# WavePainter_1_1.net
KiCad netlist of a schematic drawn in EAGLE
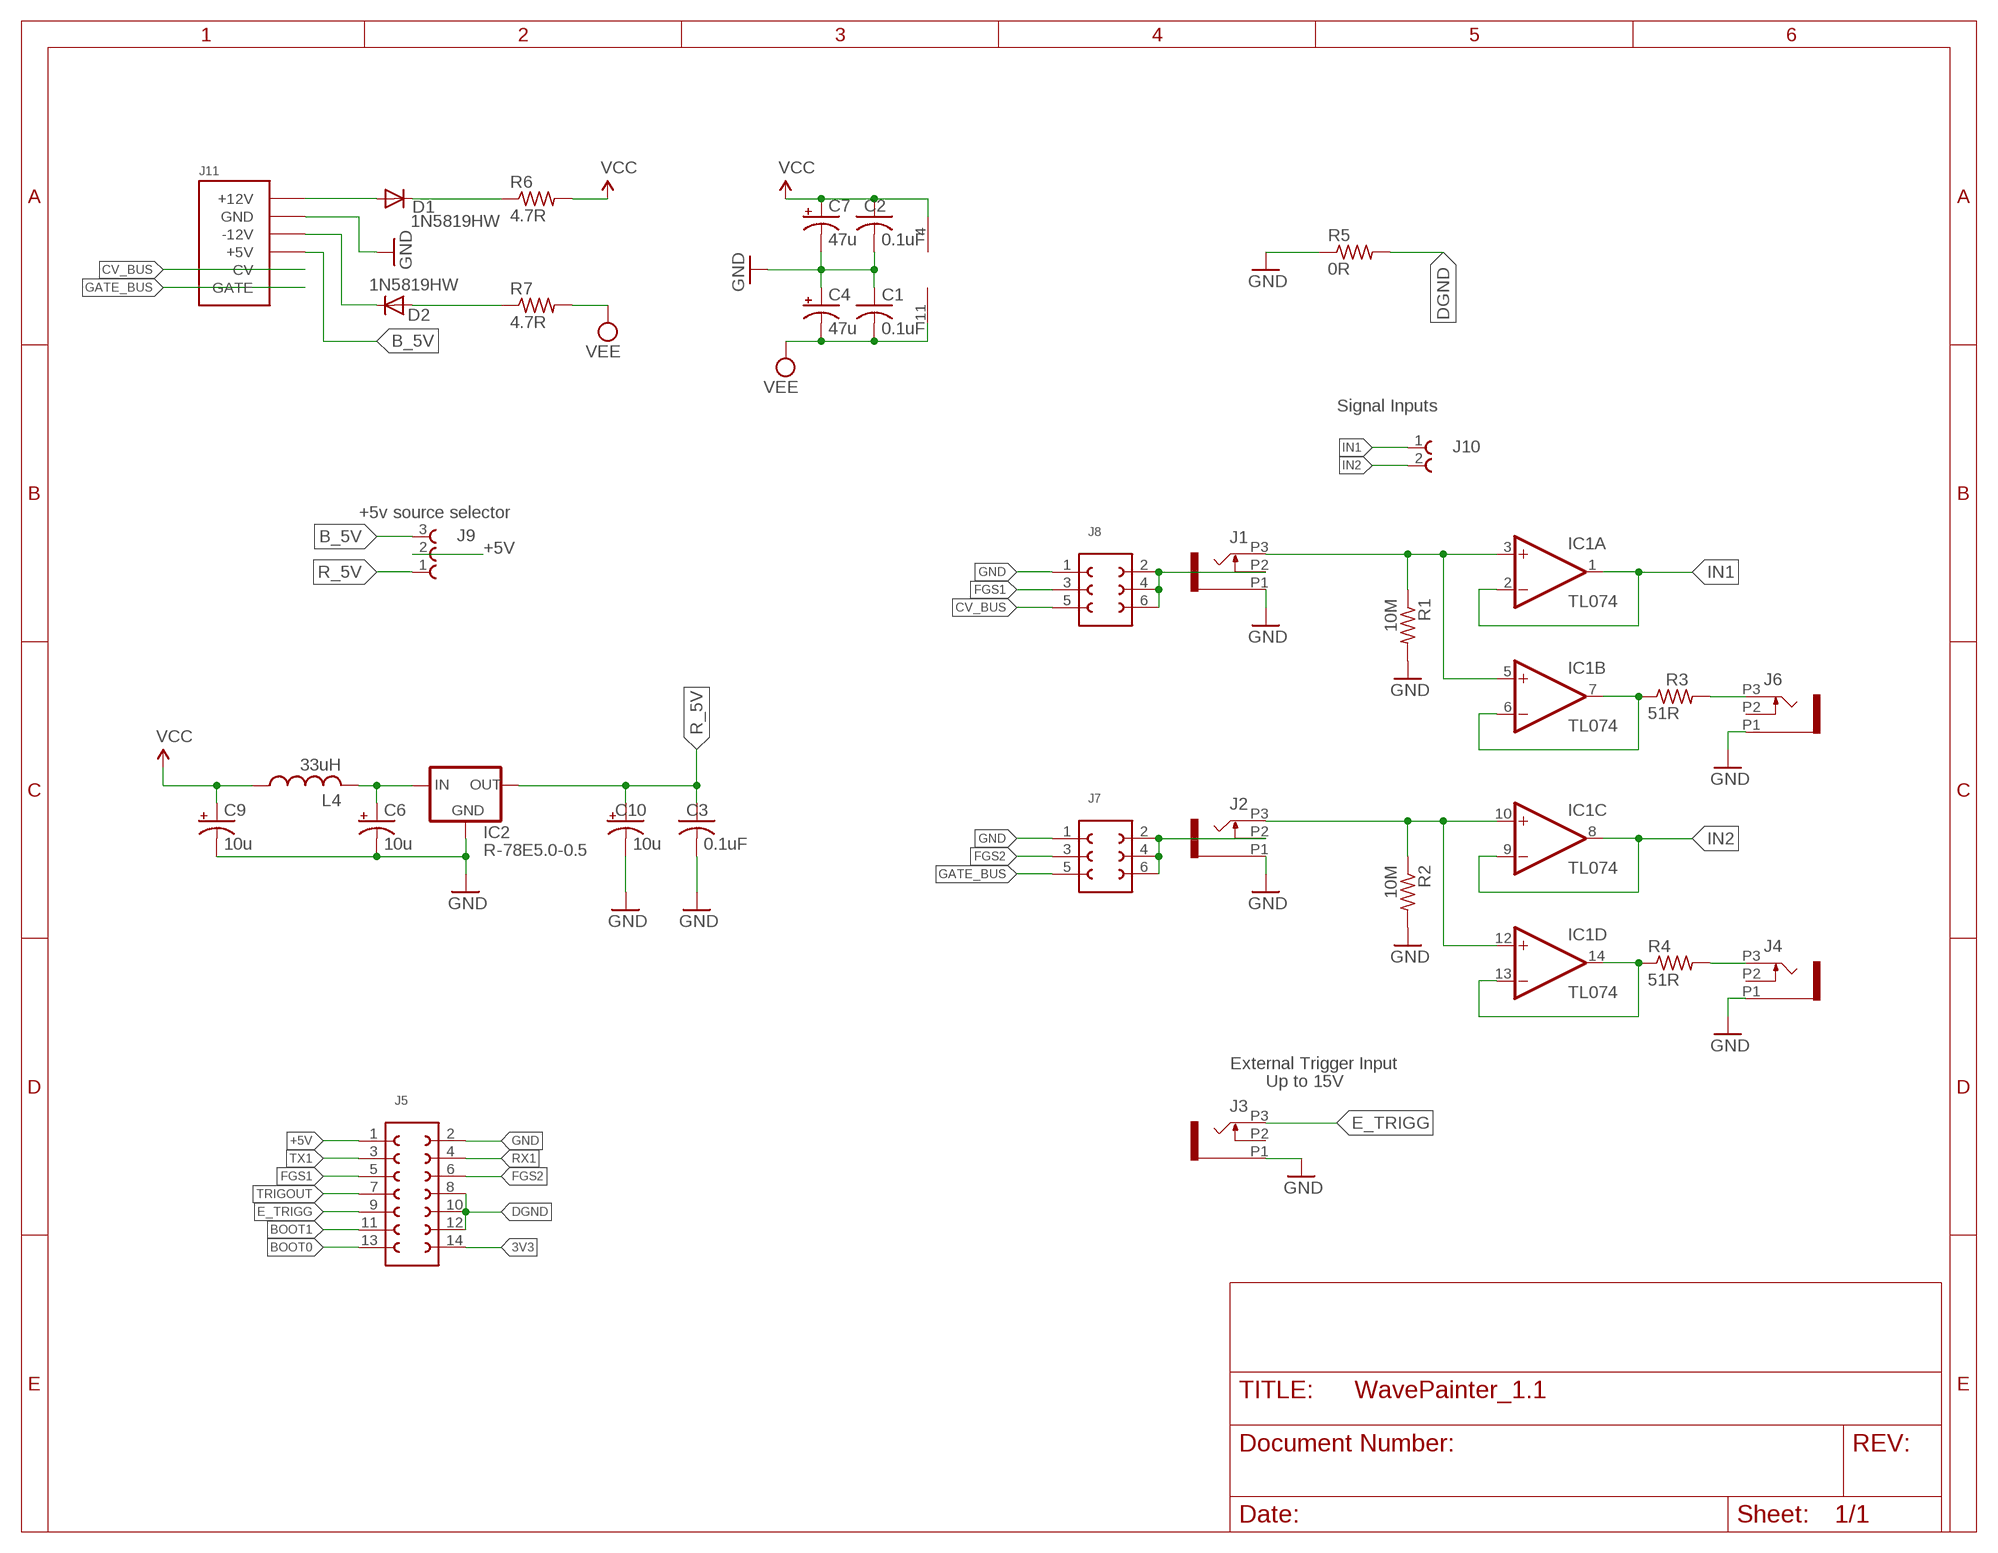
[diagram p0: schematic, sheet 1]

(export (version "E")
  (design (tool "Eeschema 10.0.6"))
  (components
    (comp (ref "C1")
      (value "0.1uF")
      (footprint "eagle-import:C0805")
      (libsource (lib "eagle-import") (part "C-USC0805"))
    )
    (comp (ref "C2")
      (value "0.1uF")
      (footprint "eagle-import:C0805")
      (libsource (lib "eagle-import") (part "C-USC0805"))
    )
    (comp (ref "C3")
      (value "0.1uF")
      (footprint "eagle-import:C0805")
      (libsource (lib "eagle-import") (part "C-USC0805"))
    )
    (comp (ref "C4")
      (value "47u")
      (footprint "eagle-import:PANASONIC_D")
      (libsource (lib "eagle-import") (part "CPOL-USD"))
    )
    (comp (ref "C6")
      (value "10u")
      (footprint "eagle-import:PANASONIC_B")
      (libsource (lib "eagle-import") (part "rcl_334_CPOL-USB"))
    )
    (comp (ref "C7")
      (value "47u")
      (footprint "eagle-import:PANASONIC_D")
      (libsource (lib "eagle-import") (part "CPOL-USD"))
    )
    (comp (ref "C9")
      (value "10u")
      (footprint "eagle-import:PANASONIC_B")
      (libsource (lib "eagle-import") (part "rcl_334_CPOL-USB"))
    )
    (comp (ref "C10")
      (value "10u")
      (footprint "eagle-import:PANASONIC_B")
      (libsource (lib "eagle-import") (part "rcl_334_CPOL-USB"))
    )
    (comp (ref "D1")
      (value "1N5819HW")
      (footprint "eagle-import:DIODE_SOD123")
      (libsource (lib "eagle-import") (part "DIODE_DIODE-SOD123"))
    )
    (comp (ref "D2")
      (value "1N5819HW")
      (footprint "eagle-import:DIODE_SOD123")
      (libsource (lib "eagle-import") (part "DIODE_DIODE-SOD123"))
    )
    (comp (ref "IC1")
      (value "TL074")
      (footprint "eagle-import:SO14")
      (libsource (lib "eagle-import") (part "TL074D"))
    )
    (comp (ref "IC2")
      (value "R-78E5.0-0.5")
      (footprint "eagle-import:SIP3")
      (fields (field (name "MF") "Recom") (field (name "MPN") "R-785.0-0.5"))
      (libsource (lib "eagle-import") (part "R-78E-0.55.0"))
    )
    (comp (ref "J1")
      (value "OG-PJ301_PJ301_THONKICONN7")
      (footprint "eagle-import:OG-PJ301_WQP_PJ_301M7")
      (libsource (lib "eagle-import") (part "OG-PJ301_PJ301_THONKICONN7"))
    )
    (comp (ref "J2")
      (value "OG-PJ301_PJ301_THONKICONN7")
      (footprint "eagle-import:OG-PJ301_WQP_PJ_301M7")
      (libsource (lib "eagle-import") (part "OG-PJ301_PJ301_THONKICONN7"))
    )
    (comp (ref "J3")
      (value "OG-PJ301_PJ301_THONKICONN7")
      (footprint "eagle-import:OG-PJ301_WQP_PJ_301M7")
      (libsource (lib "eagle-import") (part "OG-PJ301_PJ301_THONKICONN7"))
    )
    (comp (ref "J4")
      (value "OG-PJ301_PJ301_THONKICONN7")
      (footprint "eagle-import:OG-PJ301_WQP_PJ_301M7")
      (libsource (lib "eagle-import") (part "OG-PJ301_PJ301_THONKICONN7"))
    )
    (comp (ref "J5")
      (value "62001421821")
      (footprint "eagle-import:62001421821")
      (libsource (lib "eagle-import") (part "62001421821"))
    )
    (comp (ref "J6")
      (value "OG-PJ301_PJ301_THONKICONN7")
      (footprint "eagle-import:OG-PJ301_WQP_PJ_301M7")
      (libsource (lib "eagle-import") (part "OG-PJ301_PJ301_THONKICONN7"))
    )
    (comp (ref "J7")
      (value "61300621121")
      (footprint "eagle-import:61300621121")
      (libsource (lib "eagle-import") (part "61300621121"))
    )
    (comp (ref "J8")
      (value "61300621121")
      (footprint "eagle-import:61300621121")
      (libsource (lib "eagle-import") (part "61300621121"))
    )
    (comp (ref "J9")
      (value "61300311121")
      (footprint "eagle-import:61300311121")
      (libsource (lib "eagle-import") (part "61300311121"))
    )
    (comp (ref "J10")
      (value "61300211821")
      (footprint "eagle-import:61300211821")
      (libsource (lib "eagle-import") (part "61300211821"))
    )
    (comp (ref "J11")
      (value "POWER_SHROUDED_NOTEXT")
      (footprint "eagle-import:POWER_16_SHROUDED_NOTEXT")
      (libsource (lib "eagle-import") (part "POWER_SHROUDED_NOTEXT"))
    )
    (comp (ref "L4")
      (value "33uH")
      (footprint "eagle-import:L3225P")
      (libsource (lib "eagle-import") (part "L-USL3225P"))
    )
    (comp (ref "R1")
      (value "10M")
      (footprint "eagle-import:R0805")
      (libsource (lib "eagle-import") (part "R-US_R0805"))
    )
    (comp (ref "R2")
      (value "10M")
      (footprint "eagle-import:R0805")
      (libsource (lib "eagle-import") (part "R-US_R0805"))
    )
    (comp (ref "R3")
      (value "51R")
      (footprint "eagle-import:R0805")
      (libsource (lib "eagle-import") (part "R-US_R0805"))
    )
    (comp (ref "R4")
      (value "51R")
      (footprint "eagle-import:R0805")
      (libsource (lib "eagle-import") (part "R-US_R0805"))
    )
    (comp (ref "R5")
      (value "0R")
      (footprint "eagle-import:R0805")
      (libsource (lib "eagle-import") (part "R-US_R0805"))
    )
    (comp (ref "R6")
      (value "4.7R")
      (footprint "eagle-import:R1206")
      (libsource (lib "eagle-import") (part "R-US_R1206"))
    )
    (comp (ref "R7")
      (value "4.7R")
      (footprint "eagle-import:R1206")
      (libsource (lib "eagle-import") (part "R-US_R1206"))
    )
  )
  (nets
    (net (code "1") (name "+5V") (class "Default")
      (node (ref "J5") (pin "1") (pinfunction "1_1") (pintype "passive"))
      (node (ref "J9") (pin "2") (pinfunction "2_2") (pintype "passive"))
    )
    (net (code "2") (name "3V3") (class "Default")
      (node (ref "J5") (pin "14") (pinfunction "8_14") (pintype "passive"))
    )
    (net (code "3") (name "BOOT0") (class "Default")
      (node (ref "J5") (pin "13") (pinfunction "7_13") (pintype "passive"))
    )
    (net (code "4") (name "BOOT1") (class "Default")
      (node (ref "J5") (pin "11") (pinfunction "6_11") (pintype "passive"))
    )
    (net (code "5") (name "B_5V") (class "Default")
      (node (ref "J11") (pin "11") (pinfunction "+5V_11") (pintype "bidirectional"))
      (node (ref "J11") (pin "12") (pinfunction "+5V_12") (pintype "bidirectional"))
      (node (ref "J9") (pin "3") (pinfunction "1_3") (pintype "passive"))
    )
    (net (code "6") (name "CV_BUS") (class "Default")
      (node (ref "J11") (pin "13") (pinfunction "CV_13") (pintype "bidirectional"))
      (node (ref "J11") (pin "14") (pinfunction "CV_14") (pintype "bidirectional"))
      (node (ref "J8") (pin "5") (pinfunction "3_5") (pintype "passive"))
    )
    (net (code "7") (name "DGND") (class "Default")
      (node (ref "J5") (pin "10") (pinfunction "10_10") (pintype "passive"))
      (node (ref "J5") (pin "12") (pinfunction "9_12") (pintype "passive"))
      (node (ref "J5") (pin "8") (pinfunction "11_8") (pintype "passive"))
      (node (ref "R5") (pin "2") (pinfunction "2_2") (pintype "passive"))
    )
    (net (code "8") (name "E_TRIGG") (class "Default")
      (node (ref "J3") (pin "P3") (pinfunction "3_P3") (pintype "passive"))
      (node (ref "J5") (pin "9") (pinfunction "5_9") (pintype "passive"))
    )
    (net (code "9") (name "FGS1") (class "Default")
      (node (ref "J5") (pin "5") (pinfunction "3_5") (pintype "passive"))
      (node (ref "J8") (pin "3") (pinfunction "2_3") (pintype "passive"))
    )
    (net (code "10") (name "FGS2") (class "Default")
      (node (ref "J5") (pin "6") (pinfunction "12_6") (pintype "passive"))
      (node (ref "J7") (pin "3") (pinfunction "2_3") (pintype "passive"))
    )
    (net (code "11") (name "GATE_BUS") (class "Default")
      (node (ref "J11") (pin "15") (pinfunction "GATE_15") (pintype "bidirectional"))
      (node (ref "J11") (pin "16") (pinfunction "GATE_16") (pintype "bidirectional"))
      (node (ref "J7") (pin "5") (pinfunction "3_5") (pintype "passive"))
    )
    (net (code "12") (name "GND") (class "Default")
      (node (ref "C1") (pin "1") (pinfunction "1_1") (pintype "passive"))
      (node (ref "C10") (pin "-") (pinfunction "-_-") (pintype "passive"))
      (node (ref "C2") (pin "2") (pinfunction "2_2") (pintype "passive"))
      (node (ref "C3") (pin "2") (pinfunction "2_2") (pintype "passive"))
      (node (ref "C4") (pin "+") (pinfunction "+_+") (pintype "passive"))
      (node (ref "C6") (pin "-") (pinfunction "-_-") (pintype "passive"))
      (node (ref "C7") (pin "-") (pinfunction "-_-") (pintype "passive"))
      (node (ref "C9") (pin "-") (pinfunction "-_-") (pintype "passive"))
      (node (ref "IC2") (pin "2") (pinfunction "GND_2") (pintype "input"))
      (node (ref "J1") (pin "P1") (pinfunction "1_P1") (pintype "passive"))
      (node (ref "J11") (pin "3") (pinfunction "GND_3") (pintype "bidirectional"))
      (node (ref "J11") (pin "4") (pinfunction "GND_4") (pintype "bidirectional"))
      (node (ref "J11") (pin "5") (pinfunction "GND_5") (pintype "bidirectional"))
      (node (ref "J11") (pin "6") (pinfunction "GND_6") (pintype "bidirectional"))
      (node (ref "J11") (pin "7") (pinfunction "GND_7") (pintype "bidirectional"))
      (node (ref "J11") (pin "8") (pinfunction "GND_8") (pintype "bidirectional"))
      (node (ref "J2") (pin "P1") (pinfunction "1_P1") (pintype "passive"))
      (node (ref "J3") (pin "P1") (pinfunction "1_P1") (pintype "passive"))
      (node (ref "J4") (pin "P1") (pinfunction "1_P1") (pintype "passive"))
      (node (ref "J5") (pin "2") (pinfunction "14_2") (pintype "passive"))
      (node (ref "J6") (pin "P1") (pinfunction "1_P1") (pintype "passive"))
      (node (ref "J7") (pin "1") (pinfunction "1_1") (pintype "passive"))
      (node (ref "J8") (pin "1") (pinfunction "1_1") (pintype "passive"))
      (node (ref "R1") (pin "2") (pinfunction "2_2") (pintype "passive"))
      (node (ref "R2") (pin "2") (pinfunction "2_2") (pintype "passive"))
      (node (ref "R5") (pin "1") (pinfunction "1_1") (pintype "passive"))
    )
    (net (code "13") (name "IN1") (class "Default")
      (node (ref "IC1") (pin "1") (pinfunction "OUT_1") (pintype "output"))
      (node (ref "IC1") (pin "2") (pinfunction "-IN_2") (pintype "input"))
      (node (ref "J10") (pin "1") (pinfunction "1_1") (pintype "passive"))
    )
    (net (code "14") (name "IN2") (class "Default")
      (node (ref "IC1") (pin "8") (pinfunction "OUT_8") (pintype "output"))
      (node (ref "IC1") (pin "9") (pinfunction "-IN_9") (pintype "input"))
      (node (ref "J10") (pin "2") (pinfunction "2_2") (pintype "passive"))
    )
    (net (code "15") (name "Net-(D1-PadA)") (class "Default")
      (node (ref "D1") (pin "A") (pinfunction "A_A") (pintype "passive"))
      (node (ref "J11") (pin "10") (pinfunction "+12V_10") (pintype "bidirectional"))
      (node (ref "J11") (pin "9") (pinfunction "+12V_9") (pintype "bidirectional"))
    )
    (net (code "16") (name "Net-(D1-PadC)") (class "Default")
      (node (ref "D1") (pin "C") (pinfunction "C_C") (pintype "passive"))
      (node (ref "R6") (pin "1") (pinfunction "1_1") (pintype "passive"))
    )
    (net (code "17") (name "Net-(D2-PadA)") (class "Default")
      (node (ref "D2") (pin "A") (pinfunction "A_A") (pintype "passive"))
      (node (ref "R7") (pin "1") (pinfunction "1_1") (pintype "passive"))
    )
    (net (code "18") (name "Net-(D2-PadC)") (class "Default")
      (node (ref "D2") (pin "C") (pinfunction "C_C") (pintype "passive"))
      (node (ref "J11") (pin "1") (pinfunction "-12V_1") (pintype "bidirectional"))
      (node (ref "J11") (pin "2") (pinfunction "-12V_2") (pintype "bidirectional"))
    )
    (net (code "19") (name "Net-(IC1A-+IN)") (class "Default")
      (node (ref "IC1") (pin "3") (pinfunction "+IN_3") (pintype "input"))
      (node (ref "IC1") (pin "5") (pinfunction "+IN_5") (pintype "input"))
      (node (ref "J1") (pin "P3") (pinfunction "3_P3") (pintype "passive"))
      (node (ref "R1") (pin "1") (pinfunction "1_1") (pintype "passive"))
    )
    (net (code "20") (name "Net-(IC1B--IN)") (class "Default")
      (node (ref "IC1") (pin "6") (pinfunction "-IN_6") (pintype "input"))
      (node (ref "IC1") (pin "7") (pinfunction "OUT_7") (pintype "output"))
      (node (ref "R3") (pin "1") (pinfunction "1_1") (pintype "passive"))
    )
    (net (code "21") (name "Net-(IC1C-+IN)") (class "Default")
      (node (ref "IC1") (pin "10") (pinfunction "+IN_10") (pintype "input"))
      (node (ref "IC1") (pin "12") (pinfunction "+IN_12") (pintype "input"))
      (node (ref "J2") (pin "P3") (pinfunction "3_P3") (pintype "passive"))
      (node (ref "R2") (pin "1") (pinfunction "1_1") (pintype "passive"))
    )
    (net (code "22") (name "Net-(IC1D--IN)") (class "Default")
      (node (ref "IC1") (pin "13") (pinfunction "-IN_13") (pintype "input"))
      (node (ref "IC1") (pin "14") (pinfunction "OUT_14") (pintype "output"))
      (node (ref "R4") (pin "1") (pinfunction "1_1") (pintype "passive"))
    )
    (net (code "23") (name "Net-(IC2-IN)") (class "Default")
      (node (ref "C6") (pin "+") (pinfunction "+_+") (pintype "passive"))
      (node (ref "IC2") (pin "1") (pinfunction "IN_1") (pintype "input"))
      (node (ref "L4") (pin "2") (pinfunction "2_2") (pintype "passive"))
    )
    (net (code "24") (name "Net-(J1-2)") (class "Default")
      (node (ref "J1") (pin "P2") (pinfunction "2_P2") (pintype "passive"))
      (node (ref "J8") (pin "2") (pinfunction "6_2") (pintype "passive"))
      (node (ref "J8") (pin "4") (pinfunction "5_4") (pintype "passive"))
      (node (ref "J8") (pin "6") (pinfunction "4_6") (pintype "passive"))
    )
    (net (code "25") (name "Net-(J2-2)") (class "Default")
      (node (ref "J2") (pin "P2") (pinfunction "2_P2") (pintype "passive"))
      (node (ref "J7") (pin "2") (pinfunction "6_2") (pintype "passive"))
      (node (ref "J7") (pin "4") (pinfunction "5_4") (pintype "passive"))
      (node (ref "J7") (pin "6") (pinfunction "4_6") (pintype "passive"))
    )
    (net (code "26") (name "Net-(J4-3)") (class "Default")
      (node (ref "J4") (pin "P3") (pinfunction "3_P3") (pintype "passive"))
      (node (ref "R4") (pin "2") (pinfunction "2_2") (pintype "passive"))
    )
    (net (code "27") (name "Net-(J6-3)") (class "Default")
      (node (ref "J6") (pin "P3") (pinfunction "3_P3") (pintype "passive"))
      (node (ref "R3") (pin "2") (pinfunction "2_2") (pintype "passive"))
    )
    (net (code "28") (name "RX1") (class "Default")
      (node (ref "J5") (pin "4") (pinfunction "13_4") (pintype "passive"))
    )
    (net (code "29") (name "R_5V") (class "Default")
      (node (ref "C10") (pin "+") (pinfunction "+_+") (pintype "passive"))
      (node (ref "C3") (pin "1") (pinfunction "1_1") (pintype "passive"))
      (node (ref "IC2") (pin "3") (pinfunction "OUT_3") (pintype "passive"))
      (node (ref "J9") (pin "1") (pinfunction "3_1") (pintype "passive"))
    )
    (net (code "30") (name "TRIGOUT") (class "Default")
      (node (ref "J5") (pin "7") (pinfunction "4_7") (pintype "passive"))
    )
    (net (code "31") (name "TX1") (class "Default")
      (node (ref "J5") (pin "3") (pinfunction "2_3") (pintype "passive"))
    )
    (net (code "32") (name "VCC") (class "Default")
      (node (ref "C2") (pin "1") (pinfunction "1_1") (pintype "passive"))
      (node (ref "C7") (pin "+") (pinfunction "+_+") (pintype "passive"))
      (node (ref "C9") (pin "+") (pinfunction "+_+") (pintype "passive"))
      (node (ref "IC1") (pin "4") (pinfunction "V+_4") (pintype "power_in"))
      (node (ref "L4") (pin "1") (pinfunction "1_1") (pintype "passive"))
      (node (ref "R6") (pin "2") (pinfunction "2_2") (pintype "passive"))
    )
    (net (code "33") (name "VEE") (class "Default")
      (node (ref "C1") (pin "2") (pinfunction "2_2") (pintype "passive"))
      (node (ref "C4") (pin "-") (pinfunction "-_-") (pintype "passive"))
      (node (ref "IC1") (pin "11") (pinfunction "V-_11") (pintype "power_in"))
      (node (ref "R7") (pin "2") (pinfunction "2_2") (pintype "passive"))
    )
    (net (code "34") (name "unconnected-(J3-2-PadP2)") (class "Default")
      (node (ref "J3") (pin "P2") (pinfunction "2_P2") (pintype "passive"))
    )
    (net (code "35") (name "unconnected-(J4-2-PadP2)") (class "Default")
      (node (ref "J4") (pin "P2") (pinfunction "2_P2") (pintype "passive"))
    )
    (net (code "36") (name "unconnected-(J6-2-PadP2)") (class "Default")
      (node (ref "J6") (pin "P2") (pinfunction "2_P2") (pintype "passive"))
    )
  )
)
